# Processor.net
KiCad netlist of a schematic drawn in Altium Designer
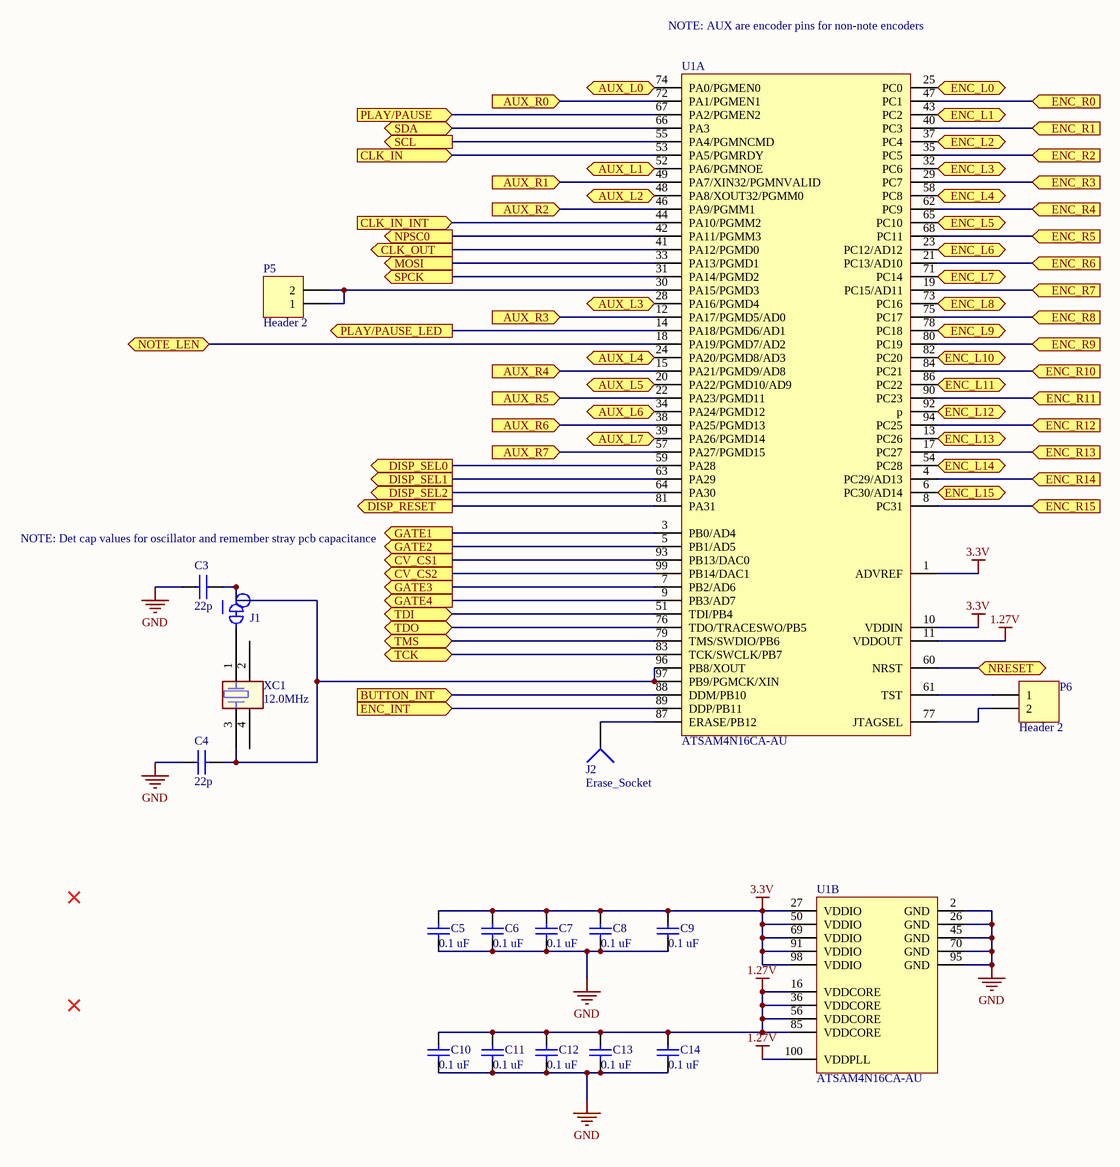
[diagram p0: Processor.SchDoc]

(export (version "E")
  (design (tool "Eeschema 10.0.6"))
  (components
    (comp (ref "C3")
      (value "22p")
      (footprint "AP1-00001")
      (description "Ceramic capacitor, SMD 0402, NP0, 50V, +/-5%")
      (fields (field (name "TOLERANCE") "50V, +/-5%") (field (name "Comment") "CAP-NONPOL"))
      (libsource (lib "AltiumDbLib") (part "CAP-NONPOL"))
    )
    (comp (ref "C4")
      (value "22p")
      (footprint "AP1-00001")
      (description "Ceramic capacitor, SMD 0402, NP0, 50V, +/-5%")
      (fields (field (name "TOLERANCE") "50V, +/-5%") (field (name "Comment") "CAP-NONPOL"))
      (libsource (lib "AltiumDbLib") (part "CAP-NONPOL"))
    )
    (comp (ref "C5")
      (value "0.1 uF")
      (footprint "C0805")
      (description "Capacitor")
      (fields (field (name "PUBLISHER") "Altium Limited"))
      (libsource (lib "Miscellaneous Devices") (part "Cap"))
    )
    (comp (ref "C6")
      (value "0.1 uF")
      (footprint "C0805")
      (description "Capacitor")
      (fields (field (name "PUBLISHER") "Altium Limited"))
      (libsource (lib "Miscellaneous Devices") (part "Cap"))
    )
    (comp (ref "C7")
      (value "0.1 uF")
      (footprint "C0805")
      (description "Capacitor")
      (fields (field (name "PUBLISHER") "Altium Limited"))
      (libsource (lib "Miscellaneous Devices") (part "Cap"))
    )
    (comp (ref "C8")
      (value "0.1 uF")
      (footprint "C0805")
      (description "Capacitor")
      (fields (field (name "PUBLISHER") "Altium Limited"))
      (libsource (lib "Miscellaneous Devices") (part "Cap"))
    )
    (comp (ref "C9")
      (value "0.1 uF")
      (footprint "C0805")
      (description "Capacitor")
      (fields (field (name "PUBLISHER") "Altium Limited"))
      (libsource (lib "Miscellaneous Devices") (part "Cap"))
    )
    (comp (ref "C10")
      (value "0.1 uF")
      (footprint "C0805")
      (description "Capacitor")
      (fields (field (name "PUBLISHER") "Altium Limited"))
      (libsource (lib "Miscellaneous Devices") (part "Cap"))
    )
    (comp (ref "C11")
      (value "0.1 uF")
      (footprint "C0805")
      (description "Capacitor")
      (fields (field (name "PUBLISHER") "Altium Limited"))
      (libsource (lib "Miscellaneous Devices") (part "Cap"))
    )
    (comp (ref "C12")
      (value "0.1 uF")
      (footprint "C0805")
      (description "Capacitor")
      (fields (field (name "PUBLISHER") "Altium Limited"))
      (libsource (lib "Miscellaneous Devices") (part "Cap"))
    )
    (comp (ref "C13")
      (value "0.1 uF")
      (footprint "C0805")
      (description "Capacitor")
      (fields (field (name "PUBLISHER") "Altium Limited"))
      (libsource (lib "Miscellaneous Devices") (part "Cap"))
    )
    (comp (ref "C14")
      (value "0.1 uF")
      (footprint "C0805")
      (description "Capacitor")
      (fields (field (name "PUBLISHER") "Altium Limited"))
      (libsource (lib "Miscellaneous Devices") (part "Cap"))
    )
    (comp (ref "J1")
      (value "SMD-STRAP_CLOSED")
      (footprint "AP9-00044")
      (description "Default closed SMD strap, 0603 size")
      (libsource (lib "AltiumDbLib") (part "SMD-STRAP_CLOSED"))
    )
    (comp (ref "J2")
      (value "Erase_Socket")
      (footprint "PIN1")
      (description "Socket")
      (fields (field (name "PUBLISHER") "Altium Limited"))
      (libsource (lib "Miscellaneous Connectors") (part "Socket"))
    )
    (comp (ref "P5")
      (value "Header 2")
      (footprint "HDR1X2")
      (description "Header, 2-Pin")
      (fields (field (name "PUBLISHER") "Altium Limited"))
      (libsource (lib "Miscellaneous Connectors") (part "Header 2"))
    )
    (comp (ref "P6")
      (value "Header 2")
      (footprint "HDR1X2")
      (description "Header, 2-Pin")
      (fields (field (name "PUBLISHER") "Altium Limited"))
      (libsource (lib "") (part "Header 2_1"))
    )
    (comp (ref "U1")
      (value "ATSAM4N16CA-AU")
      (footprint "LQFP100_N")
      (libsource (lib "Atmel Microcontroller ARM") (part "ATSAM4S16CA-AU"))
    )
    (comp (ref "XC1")
      (value "12.0MHz")
      (footprint "AP7-00039")
      (description "Fox FQ5032B 12.0MHz SMD crystal 738B-12")
      (fields (field (name "TOLERANCE") "30PPM") (field (name "MANUFACTURER") "Fox  Electronics"))
      (libsource (lib "AltiumDbLib") (part "CRYSTAL1324"))
    )
  )
  (nets
    (net (code "1") (name "/AUX_L0") (class "Default")
      (node (ref "U1") (pin "74") (pinfunction "PA0/PGMEN0_74") (pintype "passive"))
    )
    (net (code "2") (name "/AUX_L1") (class "Default")
      (node (ref "U1") (pin "52") (pinfunction "PA6/PGMNOE_52") (pintype "passive"))
    )
    (net (code "3") (name "/AUX_L2") (class "Default")
      (node (ref "U1") (pin "48") (pinfunction "PA8/XOUT32/PGMM0_48") (pintype "passive"))
    )
    (net (code "4") (name "/AUX_L3") (class "Default")
      (node (ref "U1") (pin "28") (pinfunction "PA16/PGMD4_28") (pintype "passive"))
    )
    (net (code "5") (name "/AUX_L4") (class "Default")
      (node (ref "U1") (pin "24") (pinfunction "PA20/PGMD8/AD3_24") (pintype "passive"))
    )
    (net (code "6") (name "/AUX_L5") (class "Default")
      (node (ref "U1") (pin "20") (pinfunction "PA22/PGMD10/AD9_20") (pintype "passive"))
    )
    (net (code "7") (name "/AUX_L6") (class "Default")
      (node (ref "U1") (pin "34") (pinfunction "PA24/PGMD12_34") (pintype "passive"))
    )
    (net (code "8") (name "/AUX_L7") (class "Default")
      (node (ref "U1") (pin "39") (pinfunction "PA26/PGMD14_39") (pintype "passive"))
    )
    (net (code "9") (name "/AUX_R0") (class "Default")
      (node (ref "U1") (pin "72") (pinfunction "PA1/PGMEN1_72") (pintype "passive"))
    )
    (net (code "10") (name "/AUX_R1") (class "Default")
      (node (ref "U1") (pin "49") (pinfunction "PA7/XIN32/PGMNVALID_49") (pintype "passive"))
    )
    (net (code "11") (name "/AUX_R2") (class "Default")
      (node (ref "U1") (pin "46") (pinfunction "PA9/PGMM1_46") (pintype "passive"))
    )
    (net (code "12") (name "/AUX_R3") (class "Default")
      (node (ref "U1") (pin "12") (pinfunction "PA17/PGMD5/AD0_12") (pintype "passive"))
    )
    (net (code "13") (name "/AUX_R4") (class "Default")
      (node (ref "U1") (pin "15") (pinfunction "PA21/PGMD9/AD8_15") (pintype "passive"))
    )
    (net (code "14") (name "/AUX_R5") (class "Default")
      (node (ref "U1") (pin "22") (pinfunction "PA23/PGMD11_22") (pintype "passive"))
    )
    (net (code "15") (name "/AUX_R6") (class "Default")
      (node (ref "U1") (pin "38") (pinfunction "PA25/PGMD13_38") (pintype "passive"))
    )
    (net (code "16") (name "/AUX_R7") (class "Default")
      (node (ref "U1") (pin "57") (pinfunction "PA27/PGMD15_57") (pintype "passive"))
    )
    (net (code "17") (name "/BUTTON_INT") (class "Default")
      (node (ref "U1") (pin "88") (pinfunction "DDM/PB10_88") (pintype "passive"))
    )
    (net (code "18") (name "/CLK_IN") (class "Default")
      (node (ref "U1") (pin "53") (pinfunction "PA5/PGMRDY_53") (pintype "passive"))
    )
    (net (code "19") (name "/CLK_IN_INT") (class "Default")
      (node (ref "U1") (pin "44") (pinfunction "PA10/PGMM2_44") (pintype "passive"))
    )
    (net (code "20") (name "/CLK_OUT") (class "Default")
      (node (ref "U1") (pin "41") (pinfunction "PA12/PGMD0_41") (pintype "passive"))
    )
    (net (code "21") (name "/CV_CS1") (class "Default")
      (node (ref "U1") (pin "93") (pinfunction "PB13/DAC0_93") (pintype "passive"))
    )
    (net (code "22") (name "/CV_CS2") (class "Default")
      (node (ref "U1") (pin "99") (pinfunction "PB14/DAC1_99") (pintype "passive"))
    )
    (net (code "23") (name "/DISP_RESET") (class "Default")
      (node (ref "U1") (pin "81") (pinfunction "PA31_81") (pintype "passive"))
    )
    (net (code "24") (name "/DISP_SEL0") (class "Default")
      (node (ref "U1") (pin "59") (pinfunction "PA28_59") (pintype "passive"))
    )
    (net (code "25") (name "/DISP_SEL1") (class "Default")
      (node (ref "U1") (pin "63") (pinfunction "PA29_63") (pintype "passive"))
    )
    (net (code "26") (name "/DISP_SEL2") (class "Default")
      (node (ref "U1") (pin "64") (pinfunction "PA30_64") (pintype "passive"))
    )
    (net (code "27") (name "/ENC_INT") (class "Default")
      (node (ref "U1") (pin "89") (pinfunction "DDP/PB11_89") (pintype "passive"))
    )
    (net (code "28") (name "/ENC_L0") (class "Default")
      (node (ref "U1") (pin "25") (pinfunction "PC0_25") (pintype "passive"))
    )
    (net (code "29") (name "/ENC_L1") (class "Default")
      (node (ref "U1") (pin "43") (pinfunction "PC2_43") (pintype "passive"))
    )
    (net (code "30") (name "/ENC_L2") (class "Default")
      (node (ref "U1") (pin "37") (pinfunction "PC4_37") (pintype "passive"))
    )
    (net (code "31") (name "/ENC_L3") (class "Default")
      (node (ref "U1") (pin "32") (pinfunction "PC6_32") (pintype "passive"))
    )
    (net (code "32") (name "/ENC_L4") (class "Default")
      (node (ref "U1") (pin "58") (pinfunction "PC8_58") (pintype "passive"))
    )
    (net (code "33") (name "/ENC_L5") (class "Default")
      (node (ref "U1") (pin "65") (pinfunction "PC10_65") (pintype "passive"))
    )
    (net (code "34") (name "/ENC_L6") (class "Default")
      (node (ref "U1") (pin "23") (pinfunction "PC12/AD12_23") (pintype "passive"))
    )
    (net (code "35") (name "/ENC_L7") (class "Default")
      (node (ref "U1") (pin "71") (pinfunction "PC14_71") (pintype "passive"))
    )
    (net (code "36") (name "/ENC_L8") (class "Default")
      (node (ref "U1") (pin "73") (pinfunction "PC16_73") (pintype "passive"))
    )
    (net (code "37") (name "/ENC_L9") (class "Default")
      (node (ref "U1") (pin "78") (pinfunction "PC18_78") (pintype "passive"))
    )
    (net (code "38") (name "/ENC_L10") (class "Default")
      (node (ref "U1") (pin "82") (pinfunction "PC20_82") (pintype "passive"))
    )
    (net (code "39") (name "/ENC_L11") (class "Default")
      (node (ref "U1") (pin "86") (pinfunction "PC22_86") (pintype "passive"))
    )
    (net (code "40") (name "/ENC_L12") (class "Default")
      (node (ref "U1") (pin "92") (pinfunction "p_92") (pintype "passive"))
    )
    (net (code "41") (name "/ENC_L13") (class "Default")
      (node (ref "U1") (pin "13") (pinfunction "PC26_13") (pintype "passive"))
    )
    (net (code "42") (name "/ENC_L14") (class "Default")
      (node (ref "U1") (pin "54") (pinfunction "PC28_54") (pintype "passive"))
    )
    (net (code "43") (name "/ENC_L15") (class "Default")
      (node (ref "U1") (pin "6") (pinfunction "PC30/AD14_6") (pintype "passive"))
    )
    (net (code "44") (name "/ENC_R0") (class "Default")
      (node (ref "U1") (pin "47") (pinfunction "PC1_47") (pintype "passive"))
    )
    (net (code "45") (name "/ENC_R1") (class "Default")
      (node (ref "U1") (pin "40") (pinfunction "PC3_40") (pintype "passive"))
    )
    (net (code "46") (name "/ENC_R2") (class "Default")
      (node (ref "U1") (pin "35") (pinfunction "PC5_35") (pintype "passive"))
    )
    (net (code "47") (name "/ENC_R3") (class "Default")
      (node (ref "U1") (pin "29") (pinfunction "PC7_29") (pintype "passive"))
    )
    (net (code "48") (name "/ENC_R4") (class "Default")
      (node (ref "U1") (pin "62") (pinfunction "PC9_62") (pintype "passive"))
    )
    (net (code "49") (name "/ENC_R5") (class "Default")
      (node (ref "U1") (pin "68") (pinfunction "PC11_68") (pintype "passive"))
    )
    (net (code "50") (name "/ENC_R6") (class "Default")
      (node (ref "U1") (pin "21") (pinfunction "PC13/AD10_21") (pintype "passive"))
    )
    (net (code "51") (name "/ENC_R7") (class "Default")
      (node (ref "U1") (pin "19") (pinfunction "PC15/AD11_19") (pintype "passive"))
    )
    (net (code "52") (name "/ENC_R8") (class "Default")
      (node (ref "U1") (pin "75") (pinfunction "PC17_75") (pintype "passive"))
    )
    (net (code "53") (name "/ENC_R9") (class "Default")
      (node (ref "U1") (pin "80") (pinfunction "PC19_80") (pintype "passive"))
    )
    (net (code "54") (name "/ENC_R10") (class "Default")
      (node (ref "U1") (pin "84") (pinfunction "PC21_84") (pintype "passive"))
    )
    (net (code "55") (name "/ENC_R11") (class "Default")
      (node (ref "U1") (pin "90") (pinfunction "PC23_90") (pintype "passive"))
    )
    (net (code "56") (name "/ENC_R12") (class "Default")
      (node (ref "U1") (pin "94") (pinfunction "PC25_94") (pintype "passive"))
    )
    (net (code "57") (name "/ENC_R13") (class "Default")
      (node (ref "U1") (pin "17") (pinfunction "PC27_17") (pintype "passive"))
    )
    (net (code "58") (name "/ENC_R14") (class "Default")
      (node (ref "U1") (pin "4") (pinfunction "PC29/AD13_4") (pintype "passive"))
    )
    (net (code "59") (name "/ENC_R15") (class "Default")
      (node (ref "U1") (pin "8") (pinfunction "PC31_8") (pintype "passive"))
    )
    (net (code "60") (name "/GATE1") (class "Default")
      (node (ref "U1") (pin "3") (pinfunction "PB0/AD4_3") (pintype "passive"))
    )
    (net (code "61") (name "/GATE2") (class "Default")
      (node (ref "U1") (pin "5") (pinfunction "PB1/AD5_5") (pintype "passive"))
    )
    (net (code "62") (name "/GATE3") (class "Default")
      (node (ref "U1") (pin "7") (pinfunction "PB2/AD6_7") (pintype "passive"))
    )
    (net (code "63") (name "/GATE4") (class "Default")
      (node (ref "U1") (pin "9") (pinfunction "PB3/AD7_9") (pintype "passive"))
    )
    (net (code "64") (name "/MOSI") (class "Default")
      (node (ref "U1") (pin "33") (pinfunction "PA13/PGMD1_33") (pintype "passive"))
    )
    (net (code "65") (name "/NOTE_LEN") (class "Default")
      (node (ref "U1") (pin "18") (pinfunction "PA19/PGMD7/AD2_18") (pintype "passive"))
    )
    (net (code "66") (name "/NPSC0") (class "Default")
      (node (ref "U1") (pin "42") (pinfunction "PA11/PGMM3_42") (pintype "passive"))
    )
    (net (code "67") (name "/NRESET") (class "Default")
      (node (ref "U1") (pin "60") (pinfunction "NRST_60") (pintype "passive"))
    )
    (net (code "68") (name "/PLAY{slash}PAUSE") (class "Default")
      (node (ref "U1") (pin "67") (pinfunction "PA2/PGMEN2_67") (pintype "passive"))
    )
    (net (code "69") (name "/PLAY{slash}PAUSE_LED") (class "Default")
      (node (ref "U1") (pin "14") (pinfunction "PA18/PGMD6/AD1_14") (pintype "passive"))
    )
    (net (code "70") (name "/SCL") (class "Default")
      (node (ref "U1") (pin "55") (pinfunction "PA4/PGMNCMD_55") (pintype "passive"))
    )
    (net (code "71") (name "/SDA") (class "Default")
      (node (ref "U1") (pin "66") (pinfunction "PA3_66") (pintype "passive"))
    )
    (net (code "72") (name "/SPCK") (class "Default")
      (node (ref "U1") (pin "31") (pinfunction "PA14/PGMD2_31") (pintype "passive"))
    )
    (net (code "73") (name "/TCK") (class "Default")
      (node (ref "U1") (pin "83") (pinfunction "TCK/SWCLK/PB7_83") (pintype "passive"))
    )
    (net (code "74") (name "/TDI") (class "Default")
      (node (ref "U1") (pin "51") (pinfunction "TDI/PB4_51") (pintype "passive"))
    )
    (net (code "75") (name "/TDO") (class "Default")
      (node (ref "U1") (pin "76") (pinfunction "TDO/TRACESWO/PB5_76") (pintype "passive"))
    )
    (net (code "76") (name "/TMS") (class "Default")
      (node (ref "U1") (pin "79") (pinfunction "TMS/SWDIO/PB6_79") (pintype "passive"))
    )
    (net (code "77") (name "1.27V") (class "Default")
      (node (ref "C10") (pin "2") (pinfunction "2_2") (pintype "passive"))
      (node (ref "C11") (pin "2") (pinfunction "2_2") (pintype "passive"))
      (node (ref "C12") (pin "2") (pinfunction "2_2") (pintype "passive"))
      (node (ref "C13") (pin "2") (pinfunction "2_2") (pintype "passive"))
      (node (ref "C14") (pin "2") (pinfunction "2_2") (pintype "passive"))
      (node (ref "U1") (pin "100") (pinfunction "VDDPLL_100") (pintype "power_in"))
      (node (ref "U1") (pin "11") (pinfunction "VDDOUT_11") (pintype "power_in"))
      (node (ref "U1") (pin "16") (pinfunction "VDDCORE_16") (pintype "power_in"))
      (node (ref "U1") (pin "36") (pinfunction "VDDCORE_36") (pintype "power_in"))
      (node (ref "U1") (pin "56") (pinfunction "VDDCORE_56") (pintype "power_in"))
      (node (ref "U1") (pin "85") (pinfunction "VDDCORE_85") (pintype "power_in"))
    )
    (net (code "78") (name "3.3V") (class "Default")
      (node (ref "C5") (pin "2") (pinfunction "2_2") (pintype "passive"))
      (node (ref "C6") (pin "2") (pinfunction "2_2") (pintype "passive"))
      (node (ref "C7") (pin "2") (pinfunction "2_2") (pintype "passive"))
      (node (ref "C8") (pin "2") (pinfunction "2_2") (pintype "passive"))
      (node (ref "C9") (pin "2") (pinfunction "2_2") (pintype "passive"))
      (node (ref "U1") (pin "1") (pinfunction "ADVREF_1") (pintype "passive"))
      (node (ref "U1") (pin "10") (pinfunction "VDDIN_10") (pintype "power_in"))
      (node (ref "U1") (pin "27") (pinfunction "VDDIO_27") (pintype "power_in"))
      (node (ref "U1") (pin "50") (pinfunction "VDDIO_50") (pintype "power_in"))
      (node (ref "U1") (pin "69") (pinfunction "VDDIO_69") (pintype "power_in"))
      (node (ref "U1") (pin "91") (pinfunction "VDDIO_91") (pintype "power_in"))
      (node (ref "U1") (pin "98") (pinfunction "VDDIO_98") (pintype "power_in"))
    )
    (net (code "79") (name "GND") (class "Default")
      (node (ref "C10") (pin "1") (pinfunction "1_1") (pintype "passive"))
      (node (ref "C11") (pin "1") (pinfunction "1_1") (pintype "passive"))
      (node (ref "C12") (pin "1") (pinfunction "1_1") (pintype "passive"))
      (node (ref "C13") (pin "1") (pinfunction "1_1") (pintype "passive"))
      (node (ref "C14") (pin "1") (pinfunction "1_1") (pintype "passive"))
      (node (ref "C3") (pin "2") (pinfunction "2_2") (pintype "passive"))
      (node (ref "C4") (pin "1") (pinfunction "1_1") (pintype "passive"))
      (node (ref "C5") (pin "1") (pinfunction "1_1") (pintype "passive"))
      (node (ref "C6") (pin "1") (pinfunction "1_1") (pintype "passive"))
      (node (ref "C7") (pin "1") (pinfunction "1_1") (pintype "passive"))
      (node (ref "C8") (pin "1") (pinfunction "1_1") (pintype "passive"))
      (node (ref "C9") (pin "1") (pinfunction "1_1") (pintype "passive"))
      (node (ref "U1") (pin "2") (pinfunction "GND_2") (pintype "power_in"))
      (node (ref "U1") (pin "26") (pinfunction "GND_26") (pintype "power_in"))
      (node (ref "U1") (pin "45") (pinfunction "GND_45") (pintype "power_in"))
      (node (ref "U1") (pin "70") (pinfunction "GND_70") (pintype "power_in"))
      (node (ref "U1") (pin "95") (pinfunction "GND_95") (pintype "power_in"))
    )
    (net (code "80") (name "Net-(J1-Pad2)") (class "Default")
      (node (ref "J1") (pin "2") (pinfunction "2_2") (pintype "passive"))
      (node (ref "XC1") (pin "1") (pinfunction "1_1") (pintype "passive"))
    )
    (net (code "81") (name "Net-(U1A-ERASE{slash}PB12)") (class "Default")
      (node (ref "J2") (pin "1") (pinfunction "1_1") (pintype "passive"))
      (node (ref "U1") (pin "87") (pinfunction "ERASE/PB12_87") (pintype "passive"))
    )
    (net (code "82") (name "Net-(U1A-JTAGSEL)") (class "Default")
      (node (ref "P6") (pin "2") (pinfunction "2_2") (pintype "passive"))
      (node (ref "U1") (pin "77") (pinfunction "JTAGSEL_77") (pintype "passive"))
    )
    (net (code "83") (name "Net-(U1A-PA15{slash}PGMD3)") (class "Default")
      (node (ref "P5") (pin "1") (pinfunction "1_1") (pintype "passive"))
      (node (ref "P5") (pin "2") (pinfunction "2_2") (pintype "passive"))
      (node (ref "U1") (pin "30") (pinfunction "PA15/PGMD3_30") (pintype "passive"))
    )
    (net (code "84") (name "Net-(U1A-PB8{slash}XOUT)") (class "Default")
      (node (ref "C3") (pin "1") (pinfunction "1_1") (pintype "passive"))
      (node (ref "C4") (pin "2") (pinfunction "2_2") (pintype "passive"))
      (node (ref "J1") (pin "1") (pinfunction "1_1") (pintype "passive"))
      (node (ref "U1") (pin "96") (pinfunction "PB8/XOUT_96") (pintype "passive"))
      (node (ref "U1") (pin "97") (pinfunction "PB9/PGMCK/XIN_97") (pintype "passive"))
      (node (ref "XC1") (pin "3") (pinfunction "3_3") (pintype "passive"))
    )
    (net (code "85") (name "Net-(U1A-TST)") (class "Default")
      (node (ref "P6") (pin "1") (pinfunction "1_1") (pintype "passive"))
      (node (ref "U1") (pin "61") (pinfunction "TST_61") (pintype "passive"))
    )
    (net (code "86") (name "unconnected-(XC1-Pad2)") (class "Default")
      (node (ref "XC1") (pin "2") (pinfunction "2_2") (pintype "passive"))
    )
    (net (code "87") (name "unconnected-(XC1-Pad4)") (class "Default")
      (node (ref "XC1") (pin "4") (pinfunction "4_4") (pintype "passive"))
    )
  )
)
